# HBridge.net
KiCad netlist of a schematic drawn in Altium Designer
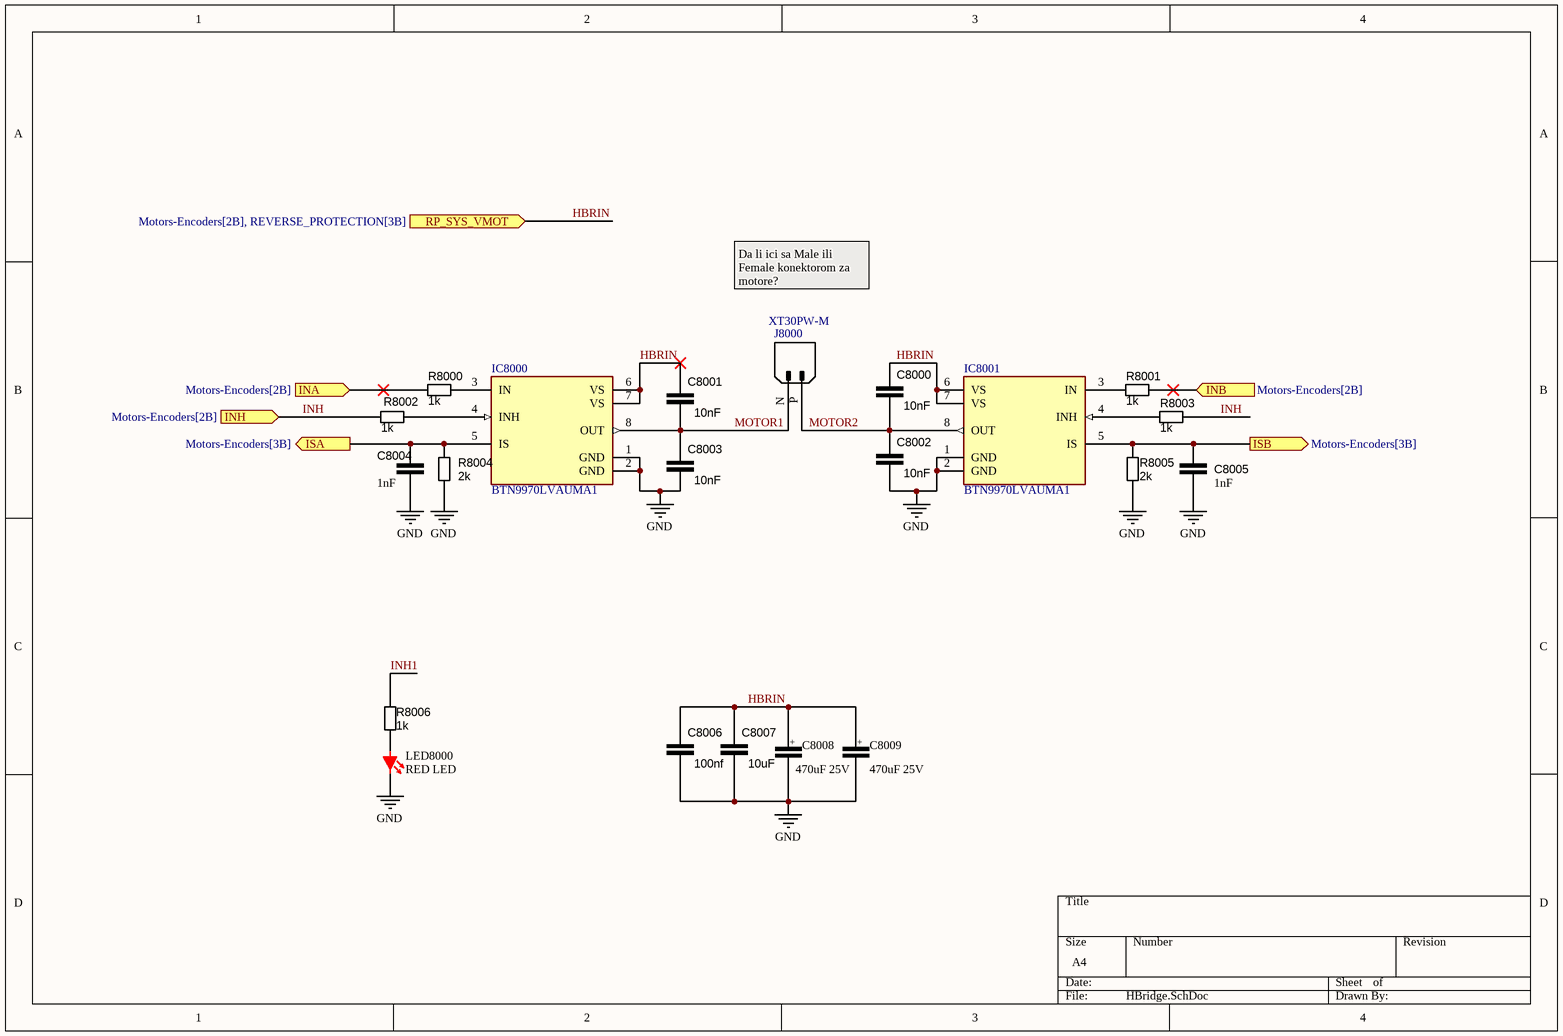
[diagram p0: HBridge.SchDoc]

(export (version "E")
  (design (tool "Eeschema 10.0.6"))
  (components
    (comp (ref "C8000")
      (value "10nF")
      (footprint "CAP_0603")
      (description "CAP CER 100nF 0603 25V X7R")
      (libsource (lib "CapacitorsIntegrated") (part "C000007"))
    )
    (comp (ref "C8001")
      (value "10nF")
      (footprint "CAP_0603")
      (description "CAP CER 100nF 0603 25V X7R")
      (libsource (lib "CapacitorsIntegrated") (part "C000007"))
    )
    (comp (ref "C8002")
      (value "10nF")
      (footprint "CAP_0603")
      (description "CAP CER 100nF 0603 25V X7R")
      (libsource (lib "CapacitorsIntegrated") (part "C000007"))
    )
    (comp (ref "C8003")
      (value "10nF")
      (footprint "CAP_0603")
      (description "CAP CER 100nF 0603 25V X7R")
      (libsource (lib "CapacitorsIntegrated") (part "C000007"))
    )
    (comp (ref "C8004")
      (value "1nF")
      (footprint "CAP_0603")
      (description "82 pF ±1% 25V Ceramic Capacitor C0G, NP0 0603 (1608 Metric)")
      (fields (field (name "DIGIKEY PART NUMBER") "478-KGM15ACG1E820FTCT-ND"))
      (libsource (lib "CapacitorsIntegrated") (part "C000021"))
    )
    (comp (ref "C8005")
      (value "1nF")
      (footprint "CAP_0603")
      (description "82 pF ±1% 25V Ceramic Capacitor C0G, NP0 0603 (1608 Metric)")
      (fields (field (name "DIGIKEY PART NUMBER") "478-KGM15ACG1E820FTCT-ND"))
      (libsource (lib "") (part "C000021_1"))
    )
    (comp (ref "C8006")
      (value "100nf")
      (footprint "CAP_0603")
      (description "CAP CER 100nF 0603 25V X7R")
      (libsource (lib "CapacitorsIntegrated") (part "C000007"))
    )
    (comp (ref "C8007")
      (value "10uF")
      (footprint "CAP_0603")
      (description "CAP CER 100nF 0603 25V X7R")
      (libsource (lib "CapacitorsIntegrated") (part "C000007"))
    )
    (comp (ref "C8008")
      (value "470uF 25V")
      (footprint "860020474014:WCAP-ATG5_8X11.5(DXL)")
      (fields
        (field (name "MF") "{'manufacturer': u'~{W}xfcrth Elektronik'}")
        (field (name "MP") "860020474014")
      )
      (libsource (lib "860020474014") (part "WCAP-ATG5_8X11.5"))
    )
    (comp (ref "C8009")
      (value "470uF 25V")
      (footprint "860020474014:WCAP-ATG5_8X11.5(DXL)")
      (fields
        (field (name "MF") "{'manufacturer': u'~{W}xfcrth Elektronik'}")
        (field (name "MP") "860020474014")
      )
      (libsource (lib "860020474014") (part "WCAP-ATG5_8X11.5"))
    )
    (comp (ref "IC8000")
      (value "BTN9970LVAUMA1")
      (footprint "FP-PG-HSOF-7-MFG")
      (description "DC_MOTOR_CONTROL PG-HSOF-7")
      (libsource (lib "Altium Content Vault") (part "34e90cea5ba01f3343ad3be64cd8383"))
    )
    (comp (ref "IC8001")
      (value "BTN9970LVAUMA1")
      (footprint "FP-PG-HSOF-7-MFG")
      (description "DC_MOTOR_CONTROL PG-HSOF-7")
      (libsource (lib "") (part "34e90cea5ba01f3343ad3be64cd8383_1"))
    )
    (comp (ref "J8000")
      (value "XT30PW-M")
      (footprint "XT30PW-M:AMASS_XT30PW-M")
      (fields (field (name "MF") "{'manufacturer': u'AMASS'}"))
      (libsource (lib "XT30PW-M") (part "XT30PW-M"))
    )
    (comp (ref "LED8000")
      (value "RED LED")
      (footprint "DIOC1608X04N")
      (description "LED RED DIFFUSED 0603 SMD")
      (libsource (lib "Miscellaneous_Lib1") (part "00000008"))
    )
    (comp (ref "R8000")
      (value "1k")
      (footprint "RES_0603")
      (description "RES 150 OHM 1% 1/10W 0603")
      (libsource (lib "ResistorsIntegrated") (part "R000004"))
    )
    (comp (ref "R8001")
      (value "1k")
      (footprint "RES_0603")
      (description "RES 150 OHM 1% 1/10W 0603")
      (libsource (lib "") (part "R000004_2"))
    )
    (comp (ref "R8002")
      (value "1k")
      (footprint "RES_0603")
      (description "RES 150 OHM 1% 1/10W 0603")
      (libsource (lib "ResistorsIntegrated") (part "R000004"))
    )
    (comp (ref "R8003")
      (value "1k")
      (footprint "RES_0603")
      (description "RES 150 OHM 1% 1/10W 0603")
      (libsource (lib "") (part "R000004_2"))
    )
    (comp (ref "R8004")
      (value "2k")
      (footprint "RES_0603")
      (description "RES 150 OHM 1% 1/10W 0603")
      (libsource (lib "") (part "R000004_1"))
    )
    (comp (ref "R8005")
      (value "2k")
      (footprint "RES_0603")
      (description "RES 150 OHM 1% 1/10W 0603")
      (libsource (lib "ResistorsIntegrated") (part "R000004"))
    )
    (comp (ref "R8006")
      (value "1k")
      (footprint "RES_0603")
      (description "RES 150 OHM 1% 1/10W 0603")
      (libsource (lib "") (part "R000004_1"))
    )
  )
  (nets
    (net (code "1") (name "/HBRIN") (class "Default")
      (node (ref "C8000") (pin "2") (pinfunction "2_2") (pintype "passive"))
      (node (ref "C8001") (pin "2") (pinfunction "2_2") (pintype "passive"))
      (node (ref "C8006") (pin "2") (pinfunction "2_2") (pintype "passive"))
      (node (ref "C8007") (pin "2") (pinfunction "2_2") (pintype "passive"))
      (node (ref "C8008") (pin "1") (pinfunction "POS_1") (pintype "passive"))
      (node (ref "C8009") (pin "1") (pinfunction "POS_1") (pintype "passive"))
      (node (ref "IC8000") (pin "6") (pinfunction "VS_6") (pintype "power_in"))
      (node (ref "IC8000") (pin "7") (pinfunction "VS_7") (pintype "power_in"))
      (node (ref "IC8001") (pin "6") (pinfunction "VS_6") (pintype "power_in"))
      (node (ref "IC8001") (pin "7") (pinfunction "VS_7") (pintype "power_in"))
    )
    (net (code "2") (name "/INA") (class "Default")
      (node (ref "R8000") (pin "2") (pinfunction "2_2") (pintype "passive"))
    )
    (net (code "3") (name "/INB") (class "Default")
      (node (ref "R8001") (pin "2") (pinfunction "2_2") (pintype "passive"))
    )
    (net (code "4") (name "/INH") (class "Default")
      (node (ref "R8002") (pin "2") (pinfunction "2_2") (pintype "passive"))
      (node (ref "R8003") (pin "2") (pinfunction "2_2") (pintype "passive"))
    )
    (net (code "5") (name "/INH1") (class "Default")
      (node (ref "R8006") (pin "1") (pinfunction "1_1") (pintype "passive"))
    )
    (net (code "6") (name "/ISA") (class "Default")
      (node (ref "C8004") (pin "2") (pinfunction "2_2") (pintype "passive"))
      (node (ref "IC8000") (pin "5") (pinfunction "IS_5") (pintype "passive"))
      (node (ref "R8004") (pin "1") (pinfunction "1_1") (pintype "passive"))
    )
    (net (code "7") (name "/ISB") (class "Default")
      (node (ref "C8005") (pin "2") (pinfunction "2_2") (pintype "passive"))
      (node (ref "IC8001") (pin "5") (pinfunction "IS_5") (pintype "passive"))
      (node (ref "R8005") (pin "1") (pinfunction "1_1") (pintype "passive"))
    )
    (net (code "8") (name "/MOTOR1") (class "Default")
      (node (ref "C8001") (pin "1") (pinfunction "1_1") (pintype "passive"))
      (node (ref "C8003") (pin "2") (pinfunction "2_2") (pintype "passive"))
      (node (ref "IC8000") (pin "8") (pinfunction "OUT_8") (pintype "output"))
      (node (ref "J8000") (pin "N") (pinfunction "N_N") (pintype "power_in"))
    )
    (net (code "9") (name "/MOTOR2") (class "Default")
      (node (ref "C8000") (pin "1") (pinfunction "1_1") (pintype "passive"))
      (node (ref "C8002") (pin "2") (pinfunction "2_2") (pintype "passive"))
      (node (ref "IC8001") (pin "8") (pinfunction "OUT_8") (pintype "output"))
      (node (ref "J8000") (pin "P") (pinfunction "P_P") (pintype "power_in"))
    )
    (net (code "10") (name "GND") (class "Default")
      (node (ref "C8002") (pin "1") (pinfunction "1_1") (pintype "passive"))
      (node (ref "C8003") (pin "1") (pinfunction "1_1") (pintype "passive"))
      (node (ref "C8004") (pin "1") (pinfunction "1_1") (pintype "passive"))
      (node (ref "C8005") (pin "1") (pinfunction "1_1") (pintype "passive"))
      (node (ref "C8006") (pin "1") (pinfunction "1_1") (pintype "passive"))
      (node (ref "C8007") (pin "1") (pinfunction "1_1") (pintype "passive"))
      (node (ref "C8008") (pin "2") (pinfunction "NEG_2") (pintype "passive"))
      (node (ref "C8009") (pin "2") (pinfunction "NEG_2") (pintype "passive"))
      (node (ref "IC8000") (pin "1") (pinfunction "GND_1") (pintype "power_in"))
      (node (ref "IC8000") (pin "2") (pinfunction "GND_2") (pintype "power_in"))
      (node (ref "IC8001") (pin "1") (pinfunction "GND_1") (pintype "power_in"))
      (node (ref "IC8001") (pin "2") (pinfunction "GND_2") (pintype "power_in"))
      (node (ref "LED8000") (pin "2") (pinfunction "2_2") (pintype "passive"))
      (node (ref "R8004") (pin "2") (pinfunction "2_2") (pintype "passive"))
      (node (ref "R8005") (pin "2") (pinfunction "2_2") (pintype "passive"))
    )
    (net (code "11") (name "Net-(IC8000-IN)") (class "Default")
      (node (ref "IC8000") (pin "3") (pinfunction "IN_3") (pintype "power_in"))
      (node (ref "R8000") (pin "1") (pinfunction "1_1") (pintype "passive"))
    )
    (net (code "12") (name "Net-(IC8000-INH)") (class "Default")
      (node (ref "IC8000") (pin "4") (pinfunction "INH_4") (pintype "input"))
      (node (ref "R8002") (pin "1") (pinfunction "1_1") (pintype "passive"))
    )
    (net (code "13") (name "Net-(IC8001-IN)") (class "Default")
      (node (ref "IC8001") (pin "3") (pinfunction "IN_3") (pintype "power_in"))
      (node (ref "R8001") (pin "1") (pinfunction "1_1") (pintype "passive"))
    )
    (net (code "14") (name "Net-(IC8001-INH)") (class "Default")
      (node (ref "IC8001") (pin "4") (pinfunction "INH_4") (pintype "input"))
      (node (ref "R8003") (pin "1") (pinfunction "1_1") (pintype "passive"))
    )
    (net (code "15") (name "Net-(LED8000-Pad1)") (class "Default")
      (node (ref "LED8000") (pin "1") (pinfunction "1_1") (pintype "passive"))
      (node (ref "R8006") (pin "2") (pinfunction "2_2") (pintype "passive"))
    )
  )
)
